# transistor-test-v2.net
KiCad netlist of a schematic drawn in EAGLE
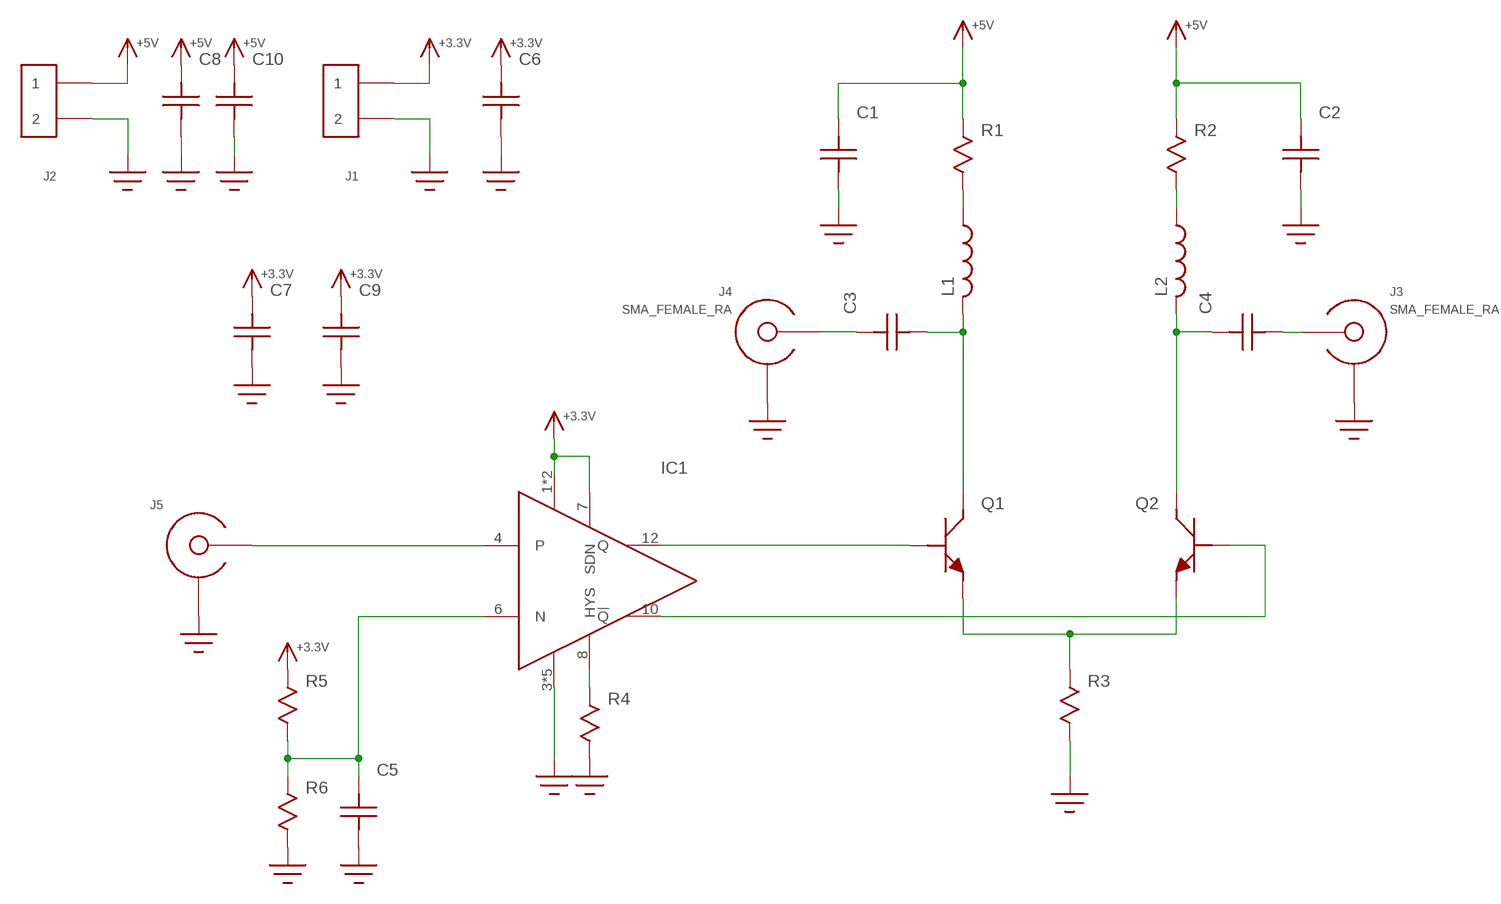
[diagram p0: schematic, sheet 1]

(export (version "E")
  (design (tool "Eeschema 10.0.6"))
  (components
    (comp (ref "C1")
      (value "C0603")
      (footprint "eagle-import:C0603")
      (libsource (lib "eagle-import") (part "C0603"))
    )
    (comp (ref "C2")
      (value "C0603")
      (footprint "eagle-import:C0603")
      (libsource (lib "eagle-import") (part "C0603"))
    )
    (comp (ref "C3")
      (value "C0603")
      (footprint "eagle-import:C0603")
      (libsource (lib "eagle-import") (part "C0603"))
    )
    (comp (ref "C4")
      (value "C0603")
      (footprint "eagle-import:C0603")
      (libsource (lib "eagle-import") (part "C0603"))
    )
    (comp (ref "C5")
      (value "C0603")
      (footprint "eagle-import:C0603")
      (libsource (lib "eagle-import") (part "C0603"))
    )
    (comp (ref "C6")
      (value "C1206")
      (footprint "eagle-import:1206")
      (libsource (lib "eagle-import") (part "C1206"))
    )
    (comp (ref "C7")
      (value "C0603")
      (footprint "eagle-import:C0603")
      (libsource (lib "eagle-import") (part "C0603"))
    )
    (comp (ref "C8")
      (value "C1206")
      (footprint "eagle-import:1206")
      (libsource (lib "eagle-import") (part "C1206"))
    )
    (comp (ref "C9")
      (value "C0603")
      (footprint "eagle-import:C0603")
      (libsource (lib "eagle-import") (part "C0603"))
    )
    (comp (ref "C10")
      (value "C1206")
      (footprint "eagle-import:1206")
      (libsource (lib "eagle-import") (part "C1206"))
    )
    (comp (ref "IC1")
      (value "ADCMP607")
      (footprint "eagle-import:QFN12-3X3")
      (libsource (lib "eagle-import") (part "ADCMP607"))
    )
    (comp (ref "J1")
      (value "HEADER_2PIN")
      (footprint "eagle-import:HEADER_2PIN")
      (libsource (lib "eagle-import") (part "HEADER_2PIN"))
    )
    (comp (ref "J2")
      (value "HEADER_2PIN")
      (footprint "eagle-import:HEADER_2PIN")
      (libsource (lib "eagle-import") (part "HEADER_2PIN"))
    )
    (comp (ref "J3")
      (value "SMA_FEMALE_RA")
      (footprint "eagle-import:SMA_RA_PCB")
      (libsource (lib "eagle-import") (part "SMA_FEMALE_RA"))
    )
    (comp (ref "J4")
      (value "SMA_FEMALE_RA")
      (footprint "eagle-import:SMA_RA_PCB")
      (libsource (lib "eagle-import") (part "SMA_FEMALE_RA"))
    )
    (comp (ref "J5")
      (value "SMA_END_LAUNCH2L")
      (footprint "eagle-import:SMA_EDGE_LAUNCH_2L")
      (libsource (lib "eagle-import") (part "SMA_END_LAUNCH2L"))
    )
    (comp (ref "L1")
      (value "INDUCTOR")
      (footprint "eagle-import:R0603")
      (libsource (lib "eagle-import") (part "INDUCTOR"))
    )
    (comp (ref "L2")
      (value "INDUCTOR")
      (footprint "eagle-import:R0603")
      (libsource (lib "eagle-import") (part "INDUCTOR"))
    )
    (comp (ref "Q1")
      (value "MCH4020")
      (footprint "eagle-import:SOT343")
      (libsource (lib "eagle-import") (part "MCH4020"))
    )
    (comp (ref "Q2")
      (value "MCH4020")
      (footprint "eagle-import:SOT343")
      (libsource (lib "eagle-import") (part "MCH4020"))
    )
    (comp (ref "R1")
      (value "R0603")
      (footprint "eagle-import:R0603")
      (libsource (lib "eagle-import") (part "R0603"))
    )
    (comp (ref "R2")
      (value "R0603")
      (footprint "eagle-import:R0603")
      (libsource (lib "eagle-import") (part "R0603"))
    )
    (comp (ref "R3")
      (value "R0603")
      (footprint "eagle-import:R0603")
      (libsource (lib "eagle-import") (part "R0603"))
    )
    (comp (ref "R4")
      (value "R0603")
      (footprint "eagle-import:R0603")
      (libsource (lib "eagle-import") (part "R0603"))
    )
    (comp (ref "R5")
      (value "R0603")
      (footprint "eagle-import:R0603")
      (libsource (lib "eagle-import") (part "R0603"))
    )
    (comp (ref "R6")
      (value "R0603")
      (footprint "eagle-import:R0603")
      (libsource (lib "eagle-import") (part "R0603"))
    )
  )
  (nets
    (net (code "1") (name "+3.3V") (class "Default")
      (node (ref "C6") (pin "P$2") (pinfunction "P$2_P$2") (pintype "bidirectional"))
      (node (ref "C7") (pin "P$2") (pinfunction "P$2_P$2") (pintype "bidirectional"))
      (node (ref "C9") (pin "P$2") (pinfunction "P$2_P$2") (pintype "bidirectional"))
      (node (ref "IC1") (pin "1") (pinfunction "VCC_1") (pintype "bidirectional"))
      (node (ref "IC1") (pin "2") (pinfunction "VCC_2") (pintype "bidirectional"))
      (node (ref "IC1") (pin "7") (pinfunction "SDN_7") (pintype "bidirectional"))
      (node (ref "J1") (pin "1") (pinfunction "1_1") (pintype "bidirectional"))
      (node (ref "R5") (pin "P$1") (pinfunction "P$3_P$1") (pintype "bidirectional"))
    )
    (net (code "2") (name "+5V") (class "Default")
      (node (ref "C1") (pin "P$2") (pinfunction "P$2_P$2") (pintype "bidirectional"))
      (node (ref "C10") (pin "P$2") (pinfunction "P$2_P$2") (pintype "bidirectional"))
      (node (ref "C2") (pin "P$2") (pinfunction "P$2_P$2") (pintype "bidirectional"))
      (node (ref "C8") (pin "P$2") (pinfunction "P$2_P$2") (pintype "bidirectional"))
      (node (ref "J2") (pin "1") (pinfunction "1_1") (pintype "bidirectional"))
      (node (ref "R1") (pin "P$1") (pinfunction "P$3_P$1") (pintype "bidirectional"))
      (node (ref "R2") (pin "P$1") (pinfunction "P$3_P$1") (pintype "bidirectional"))
    )
    (net (code "3") (name "GND") (class "Default")
      (node (ref "C1") (pin "P$1") (pinfunction "P$1_P$1") (pintype "bidirectional"))
      (node (ref "C10") (pin "P$1") (pinfunction "P$1_P$1") (pintype "bidirectional"))
      (node (ref "C2") (pin "P$1") (pinfunction "P$1_P$1") (pintype "bidirectional"))
      (node (ref "C5") (pin "P$1") (pinfunction "P$1_P$1") (pintype "bidirectional"))
      (node (ref "C6") (pin "P$1") (pinfunction "P$1_P$1") (pintype "bidirectional"))
      (node (ref "C7") (pin "P$1") (pinfunction "P$1_P$1") (pintype "bidirectional"))
      (node (ref "C8") (pin "P$1") (pinfunction "P$1_P$1") (pintype "bidirectional"))
      (node (ref "C9") (pin "P$1") (pinfunction "P$1_P$1") (pintype "bidirectional"))
      (node (ref "IC1") (pin "11") (pinfunction "VEE_11") (pintype "bidirectional"))
      (node (ref "IC1") (pin "3") (pinfunction "VEE_3") (pintype "bidirectional"))
      (node (ref "IC1") (pin "5") (pinfunction "VEE_5") (pintype "bidirectional"))
      (node (ref "IC1") (pin "9") (pinfunction "VEE_9") (pintype "bidirectional"))
      (node (ref "IC1") (pin "EP") (pinfunction "VEE_EP") (pintype "bidirectional"))
      (node (ref "J1") (pin "2") (pinfunction "2_2") (pintype "bidirectional"))
      (node (ref "J2") (pin "2") (pinfunction "2_2") (pintype "bidirectional"))
      (node (ref "J3") (pin "SHIELD@1") (pinfunction "SHIELD_SHIELD@1") (pintype "bidirectional"))
      (node (ref "J3") (pin "SHIELD@2") (pinfunction "SHIELD_SHIELD@2") (pintype "bidirectional"))
      (node (ref "J3") (pin "SHIELD@3") (pinfunction "SHIELD_SHIELD@3") (pintype "bidirectional"))
      (node (ref "J3") (pin "SHIELD@4") (pinfunction "SHIELD_SHIELD@4") (pintype "bidirectional"))
      (node (ref "J4") (pin "SHIELD@1") (pinfunction "SHIELD_SHIELD@1") (pintype "bidirectional"))
      (node (ref "J4") (pin "SHIELD@2") (pinfunction "SHIELD_SHIELD@2") (pintype "bidirectional"))
      (node (ref "J4") (pin "SHIELD@3") (pinfunction "SHIELD_SHIELD@3") (pintype "bidirectional"))
      (node (ref "J4") (pin "SHIELD@4") (pinfunction "SHIELD_SHIELD@4") (pintype "bidirectional"))
      (node (ref "J5") (pin "BOTTOM_GND") (pinfunction "SHIELD_BOTTOM_GND") (pintype "bidirectional"))
      (node (ref "J5") (pin "GND@1") (pinfunction "SHIELD_GND@1") (pintype "bidirectional"))
      (node (ref "J5") (pin "GND@11") (pinfunction "SHIELD_GND@11") (pintype "bidirectional"))
      (node (ref "J5") (pin "GND@12") (pinfunction "SHIELD_GND@12") (pintype "bidirectional"))
      (node (ref "J5") (pin "GND@14") (pinfunction "SHIELD_GND@14") (pintype "bidirectional"))
      (node (ref "J5") (pin "GND@15") (pinfunction "SHIELD_GND@15") (pintype "bidirectional"))
      (node (ref "J5") (pin "GND@16") (pinfunction "SHIELD_GND@16") (pintype "bidirectional"))
      (node (ref "J5") (pin "GND@17") (pinfunction "SHIELD_GND@17") (pintype "bidirectional"))
      (node (ref "J5") (pin "GND@2") (pinfunction "SHIELD_GND@2") (pintype "bidirectional"))
      (node (ref "J5") (pin "GND@3") (pinfunction "SHIELD_GND@3") (pintype "bidirectional"))
      (node (ref "J5") (pin "GND@4") (pinfunction "SHIELD_GND@4") (pintype "bidirectional"))
      (node (ref "J5") (pin "GND@5") (pinfunction "SHIELD_GND@5") (pintype "bidirectional"))
      (node (ref "J5") (pin "GND@6") (pinfunction "SHIELD_GND@6") (pintype "bidirectional"))
      (node (ref "J5") (pin "GND@7") (pinfunction "SHIELD_GND@7") (pintype "bidirectional"))
      (node (ref "J5") (pin "GND@8") (pinfunction "SHIELD_GND@8") (pintype "bidirectional"))
      (node (ref "J5") (pin "GND_PAD1") (pinfunction "SHIELD_GND_PAD1") (pintype "bidirectional"))
      (node (ref "J5") (pin "GND_PAD2") (pinfunction "SHIELD_GND_PAD2") (pintype "bidirectional"))
      (node (ref "R3") (pin "P$2") (pinfunction "P$4_P$2") (pintype "bidirectional"))
      (node (ref "R4") (pin "P$2") (pinfunction "P$4_P$2") (pintype "bidirectional"))
      (node (ref "R6") (pin "P$2") (pinfunction "P$4_P$2") (pintype "bidirectional"))
    )
    (net (code "4") (name "Net-(C3-PadP$2)") (class "Default")
      (node (ref "C3") (pin "P$2") (pinfunction "P$2_P$2") (pintype "bidirectional"))
      (node (ref "J4") (pin "CENTER") (pinfunction "CENTER_CENTER") (pintype "bidirectional"))
    )
    (net (code "5") (name "Net-(C4-PadP$1)") (class "Default")
      (node (ref "C4") (pin "P$1") (pinfunction "P$1_P$1") (pintype "bidirectional"))
      (node (ref "J3") (pin "CENTER") (pinfunction "CENTER_CENTER") (pintype "bidirectional"))
    )
    (net (code "6") (name "Net-(IC1-HYS)") (class "Default")
      (node (ref "IC1") (pin "8") (pinfunction "HYS_8") (pintype "bidirectional"))
      (node (ref "R4") (pin "P$1") (pinfunction "P$3_P$1") (pintype "bidirectional"))
    )
    (net (code "7") (name "Net-(IC1-N)") (class "Default")
      (node (ref "C5") (pin "P$2") (pinfunction "P$2_P$2") (pintype "bidirectional"))
      (node (ref "IC1") (pin "6") (pinfunction "N_6") (pintype "bidirectional"))
      (node (ref "R5") (pin "P$2") (pinfunction "P$4_P$2") (pintype "bidirectional"))
      (node (ref "R6") (pin "P$1") (pinfunction "P$3_P$1") (pintype "bidirectional"))
    )
    (net (code "8") (name "Net-(IC1-P)") (class "Default")
      (node (ref "IC1") (pin "4") (pinfunction "P_4") (pintype "bidirectional"))
      (node (ref "J5") (pin "CENTER@1") (pinfunction "CENTER_CENTER@1") (pintype "bidirectional"))
    )
    (net (code "9") (name "Net-(IC1-Q)") (class "Default")
      (node (ref "IC1") (pin "12") (pinfunction "Q_12") (pintype "bidirectional"))
      (node (ref "Q1") (pin "3") (pinfunction "B_3") (pintype "bidirectional"))
    )
    (net (code "10") (name "Net-(IC1-~{Q})") (class "Default")
      (node (ref "IC1") (pin "10") (pinfunction "~{Q}_10") (pintype "bidirectional"))
      (node (ref "Q2") (pin "3") (pinfunction "B_3") (pintype "bidirectional"))
    )
    (net (code "11") (name "Net-(L1-1)") (class "Default")
      (node (ref "L1") (pin "P$1") (pinfunction "1_P$1") (pintype "passive"))
      (node (ref "R1") (pin "P$2") (pinfunction "P$4_P$2") (pintype "bidirectional"))
    )
    (net (code "12") (name "Net-(L1-2)") (class "Default")
      (node (ref "C3") (pin "P$1") (pinfunction "P$1_P$1") (pintype "bidirectional"))
      (node (ref "L1") (pin "P$2") (pinfunction "2_P$2") (pintype "passive"))
      (node (ref "Q1") (pin "1") (pinfunction "C_1") (pintype "bidirectional"))
    )
    (net (code "13") (name "Net-(L2-1)") (class "Default")
      (node (ref "L2") (pin "P$1") (pinfunction "1_P$1") (pintype "passive"))
      (node (ref "R2") (pin "P$2") (pinfunction "P$4_P$2") (pintype "bidirectional"))
    )
    (net (code "14") (name "Net-(L2-2)") (class "Default")
      (node (ref "C4") (pin "P$2") (pinfunction "P$2_P$2") (pintype "bidirectional"))
      (node (ref "L2") (pin "P$2") (pinfunction "2_P$2") (pintype "passive"))
      (node (ref "Q2") (pin "1") (pinfunction "C_1") (pintype "bidirectional"))
    )
    (net (code "15") (name "Net-(R3-P$3)") (class "Default")
      (node (ref "Q1") (pin "2") (pinfunction "E_2") (pintype "bidirectional"))
      (node (ref "Q1") (pin "4") (pinfunction "E_4") (pintype "bidirectional"))
      (node (ref "Q2") (pin "2") (pinfunction "E_2") (pintype "bidirectional"))
      (node (ref "Q2") (pin "4") (pinfunction "E_4") (pintype "bidirectional"))
      (node (ref "R3") (pin "P$1") (pinfunction "P$3_P$1") (pintype "bidirectional"))
    )
  )
)
